# ardReveil4_tiny10.net
KiCad netlist of a schematic drawn in EAGLE
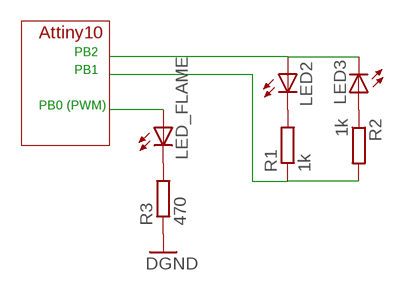
[diagram p0: schematic, sheet 1]

(export (version "E")
  (design (tool "Eeschema 10.0.6"))
  (components
    (comp (ref "LED2")
      (value "TLLY4400")
      (footprint "eagle-import:LED3MM")
      (fields (field (name "MF") "VISHAY SEMICONDUCTOR"))
      (libsource (lib "eagle-import") (part "TLLY4400"))
    )
    (comp (ref "LED3")
      (value "TLLY4400")
      (footprint "eagle-import:LED3MM")
      (fields (field (name "MF") "VISHAY SEMICONDUCTOR"))
      (libsource (lib "eagle-import") (part "TLLY4400"))
    )
    (comp (ref "LED_FLAME")
      (value "TLLY4400")
      (footprint "eagle-import:LED3MM")
      (fields (field (name "MF") "VISHAY SEMICONDUCTOR"))
      (libsource (lib "eagle-import") (part "TLLY4400"))
    )
    (comp (ref "R1")
      (value "1k")
      (footprint "eagle-import:0204_7")
      (libsource (lib "eagle-import") (part "R-EU_0204/7"))
    )
    (comp (ref "R2")
      (value "1k")
      (footprint "eagle-import:0204_7")
      (libsource (lib "eagle-import") (part "R-EU_0204/7"))
    )
    (comp (ref "R3")
      (value "470")
      (footprint "eagle-import:0204_7")
      (libsource (lib "eagle-import") (part "R-EU_0204/7"))
    )
  )
  (nets
    (net (code "1") (name "DGND") (class "Default")
      (node (ref "R3") (pin "1") (pinfunction "1_1") (pintype "passive"))
    )
    (net (code "2") (name "Net-(LED2-C)") (class "Default")
      (node (ref "LED2") (pin "K") (pinfunction "C_K") (pintype "passive"))
      (node (ref "R1") (pin "2") (pinfunction "2_2") (pintype "passive"))
    )
    (net (code "3") (name "Net-(LED3-C)") (class "Default")
      (node (ref "LED2") (pin "A") (pinfunction "A_A") (pintype "passive"))
      (node (ref "LED3") (pin "K") (pinfunction "C_K") (pintype "passive"))
    )
    (net (code "4") (name "Net-(LED3-PadA)") (class "Default")
      (node (ref "LED3") (pin "A") (pinfunction "A_A") (pintype "passive"))
      (node (ref "R2") (pin "1") (pinfunction "1_1") (pintype "passive"))
    )
    (net (code "5") (name "Net-(LED_FLAME-C)") (class "Default")
      (node (ref "LED_FLAME") (pin "K") (pinfunction "C_K") (pintype "passive"))
      (node (ref "R3") (pin "2") (pinfunction "2_2") (pintype "passive"))
    )
    (net (code "6") (name "Net-(R1-Pad1)") (class "Default")
      (node (ref "R1") (pin "1") (pinfunction "1_1") (pintype "passive"))
      (node (ref "R2") (pin "2") (pinfunction "2_2") (pintype "passive"))
    )
    (net (code "7") (name "unconnected-(LED_FLAME-PadA)") (class "Default")
      (node (ref "LED_FLAME") (pin "A") (pinfunction "A_A") (pintype "passive"))
    )
  )
)
